# IC_555_TIMER.net
KiCad netlist of a schematic drawn in Altium Designer
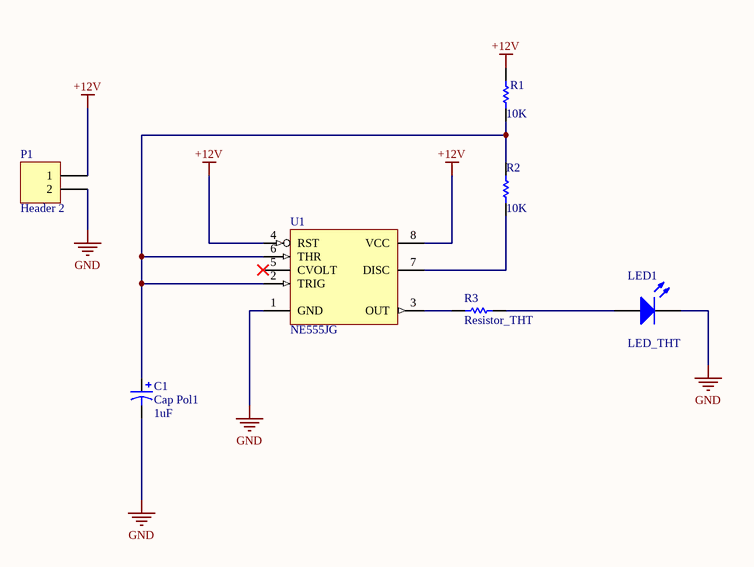
[diagram p0: IC_555_TIMER.SchDoc]

(export (version "E")
  (design (tool "Eeschema 10.0.6"))
  (components
    (comp (ref "C1")
      (value "Cap Pol1")
      (footprint "RB7.6-15")
      (description "Polarized Capacitor (Radial)")
      (fields (field (name "ALTIUM_VALUE") "1uF") (field (name "PUBLISHER") "Altium Limited"))
      (libsource (lib "Miscellaneous Devices") (part "Cap Pol1"))
    )
    (comp (ref "LED_THT")
      (value "LED1")
      (footprint "LED-1")
      (description "Typical RED GaAs LED")
      (fields (field (name "PUBLISHER") "Altium Limited"))
      (libsource (lib "Miscellaneous Devices") (part "LED1"))
    )
    (comp (ref "P1")
      (value "Header 2")
      (footprint "HDR1X2")
      (description "Header, 2-Pin")
      (fields (field (name "PUBLISHER") "Altium Limited"))
      (libsource (lib "Miscellaneous Connectors") (part "Header 2"))
    )
    (comp (ref "R1")
      (value "10K")
      (footprint "AXIAL-0.3")
      (description "Resistor")
      (fields (field (name "Comment") "G") (field (name "PUBLISHER") "Altium Limited"))
      (libsource (lib "Miscellaneous Devices") (part "Res1"))
    )
    (comp (ref "R2")
      (value "10K")
      (footprint "AXIAL-0.3")
      (description "Resistor")
      (fields (field (name "Comment") "Res1") (field (name "PUBLISHER") "Altium Limited"))
      (libsource (lib "Miscellaneous Devices") (part "Res1"))
    )
    (comp (ref "R3")
      (value "Resistor_THT")
      (footprint "AXIAL-0.3")
      (description "Resistor")
      (fields (field (name "PUBLISHER") "Altium Limited"))
      (libsource (lib "Miscellaneous Devices") (part "Res1"))
    )
    (comp (ref "U1")
      (value "NE555JG")
      (footprint "JG008")
      (description "Precision Timer")
      (fields (field (name "PUBLISHER") "Altium Limited"))
      (libsource (lib "TI Analog Timer Circuit") (part "NE555JG"))
    )
  )
  (nets
    (net (code "1") (name "+12V") (class "Default")
      (node (ref "P1") (pin "1") (pinfunction "1_1") (pintype "passive"))
      (node (ref "R1") (pin "2") (pinfunction "2_2") (pintype "passive"))
      (node (ref "U1") (pin "4") (pinfunction "RST_4") (pintype "input"))
      (node (ref "U1") (pin "8") (pinfunction "VCC_8") (pintype "power_in"))
    )
    (net (code "2") (name "GND") (class "Default")
      (node (ref "C1") (pin "2") (pinfunction "2_2") (pintype "passive"))
      (node (ref "LED_THT") (pin "2") (pinfunction "K_2") (pintype "passive"))
      (node (ref "P1") (pin "2") (pinfunction "2_2") (pintype "passive"))
      (node (ref "U1") (pin "1") (pinfunction "GND_1") (pintype "power_in"))
    )
    (net (code "3") (name "Net-(LED_THT-A)") (class "Default")
      (node (ref "LED_THT") (pin "1") (pinfunction "A_1") (pintype "passive"))
      (node (ref "R3") (pin "2") (pinfunction "2_2") (pintype "passive"))
    )
    (net (code "4") (name "Net-(U1-DISC)") (class "Default")
      (node (ref "R2") (pin "2") (pinfunction "2_2") (pintype "passive"))
      (node (ref "U1") (pin "7") (pinfunction "DISC_7") (pintype "open_collector"))
    )
    (net (code "5") (name "Net-(U1-OUT)") (class "Default")
      (node (ref "R3") (pin "1") (pinfunction "1_1") (pintype "passive"))
      (node (ref "U1") (pin "3") (pinfunction "OUT_3") (pintype "output"))
    )
    (net (code "6") (name "Net-(U1-THR)") (class "Default")
      (node (ref "C1") (pin "1") (pinfunction "1_1") (pintype "passive"))
      (node (ref "R1") (pin "1") (pinfunction "1_1") (pintype "passive"))
      (node (ref "R2") (pin "1") (pinfunction "1_1") (pintype "passive"))
      (node (ref "U1") (pin "2") (pinfunction "TRIG_2") (pintype "input"))
      (node (ref "U1") (pin "6") (pinfunction "THR_6") (pintype "input"))
    )
    (net (code "7") (name "unconnected-(U1-CVOLT-Pad5)") (class "Default")
      (node (ref "U1") (pin "5") (pinfunction "CVOLT_5") (pintype "passive+no_connect"))
    )
  )
)
